# MSP_Power_Program.net
KiCad netlist of a schematic drawn in Altium Designer
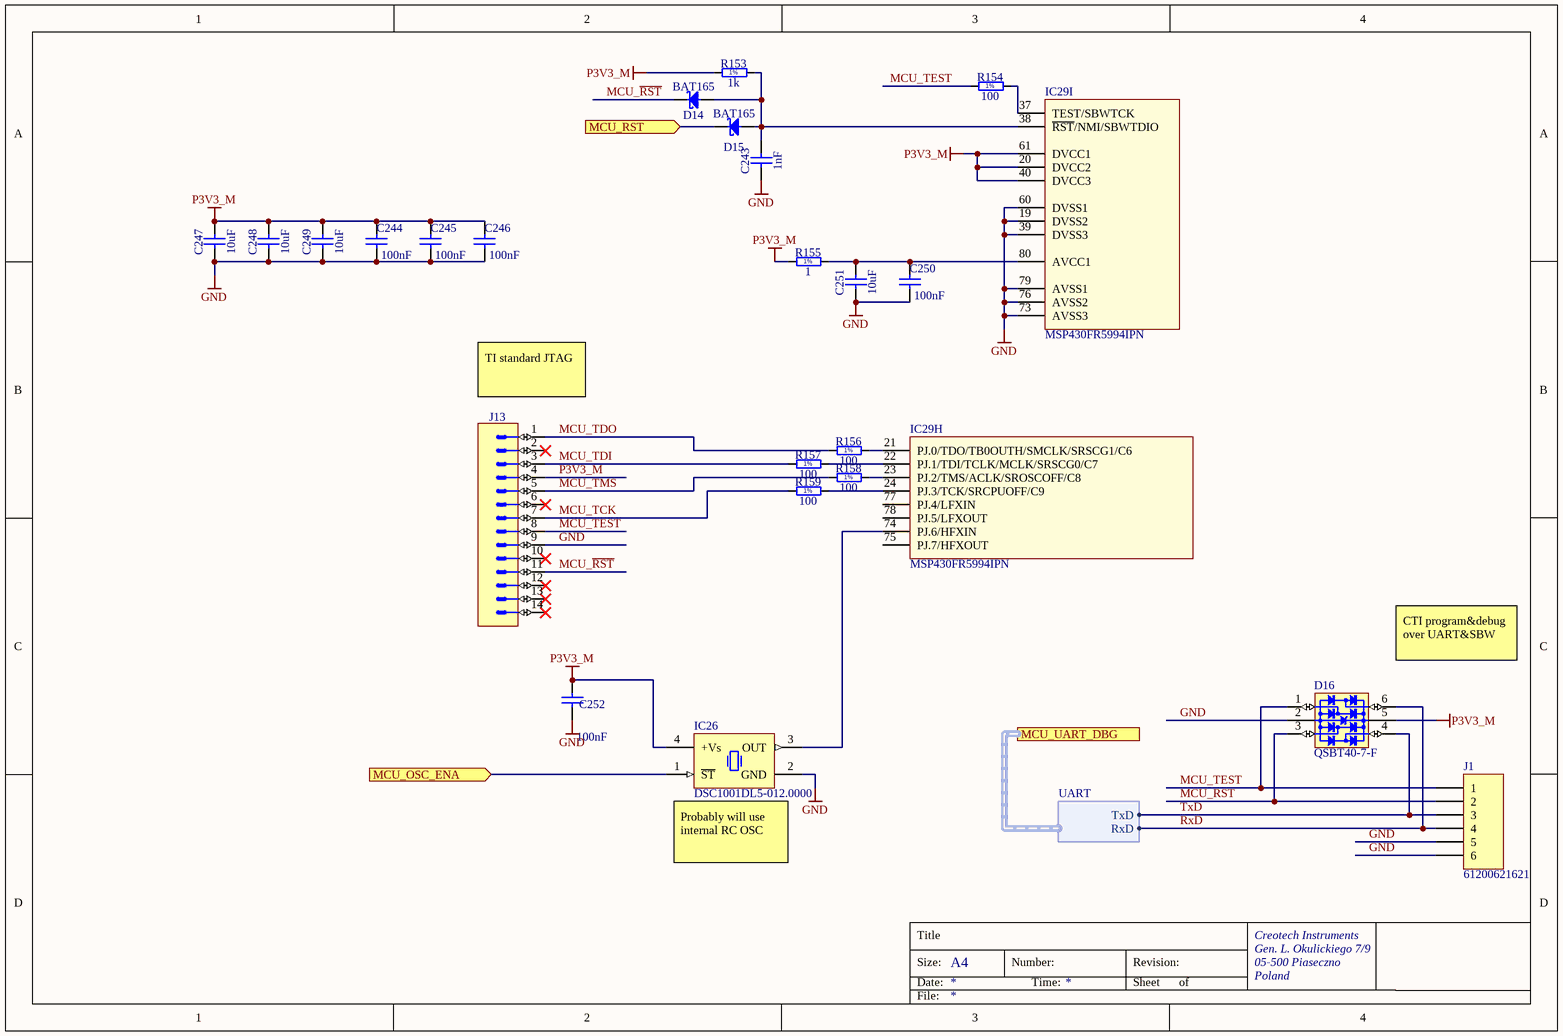
[diagram p0: MSP_Power_Program.SchDoc]

(export (version "E")
  (design (tool "Eeschema 10.0.6"))
  (components
    (comp (ref "C243")
      (value "1nF")
      (footprint "CAPC1608X87N")
      (description "Non-polarised capacitor")
      (fields
        (field (name "PART NUMBER") "CC0603_1NF_50V_10%_X7R")
        (field (name "VOLTAGE") "50V")
        (field (name "AUTHOR") "CERN DEM JLC")
      )
      (libsource (lib "Capacitors") (part "Capacitor - non polarized"))
    )
    (comp (ref "C244")
      (value "100nF")
      (footprint "CAPC1608X87N")
      (description "Non-polarised capacitor")
      (fields
        (field (name "PART NUMBER") "CC0603_100NF_50V_10%_X7R")
        (field (name "VOLTAGE") "50V")
        (field (name "AUTHOR") "CERN DEM JLC")
      )
      (libsource (lib "Capacitors") (part "Capacitor - non polarized"))
    )
    (comp (ref "C245")
      (value "100nF")
      (footprint "CAPC1608X87N")
      (description "Non-polarised capacitor")
      (fields
        (field (name "PART NUMBER") "CC0603_100NF_50V_10%_X7R")
        (field (name "VOLTAGE") "50V")
        (field (name "AUTHOR") "CERN DEM JLC")
      )
      (libsource (lib "Capacitors") (part "Capacitor - non polarized"))
    )
    (comp (ref "C246")
      (value "100nF")
      (footprint "CAPC1608X87N")
      (description "Non-polarised capacitor")
      (fields
        (field (name "PART NUMBER") "CC0603_100NF_50V_10%_X7R")
        (field (name "VOLTAGE") "50V")
        (field (name "AUTHOR") "CERN DEM JLC")
      )
      (libsource (lib "Capacitors") (part "Capacitor - non polarized"))
    )
    (comp (ref "C247")
      (value "10uF")
      (footprint "CAPC1608X80N")
      (description "Non-polarised capacitor")
      (fields
        (field (name "PART NUMBER") "CC0603_10UF_16V_20%_X5R")
        (field (name "VOLTAGE") "16V")
        (field (name "AUTHOR") "CERN DEM MR")
      )
      (libsource (lib "Capacitors") (part "Capacitor - non polarized"))
    )
    (comp (ref "C248")
      (value "10uF")
      (footprint "CAPC1608X80N")
      (description "Non-polarised capacitor")
      (fields
        (field (name "PART NUMBER") "CC0603_10UF_16V_20%_X5R")
        (field (name "VOLTAGE") "16V")
        (field (name "AUTHOR") "CERN DEM MR")
      )
      (libsource (lib "Capacitors") (part "Capacitor - non polarized"))
    )
    (comp (ref "C249")
      (value "10uF")
      (footprint "CAPC1608X80N")
      (description "Non-polarised capacitor")
      (fields
        (field (name "PART NUMBER") "CC0603_10UF_16V_20%_X5R")
        (field (name "VOLTAGE") "16V")
        (field (name "AUTHOR") "CERN DEM MR")
      )
      (libsource (lib "Capacitors") (part "Capacitor - non polarized"))
    )
    (comp (ref "C250")
      (value "100nF")
      (footprint "CAPC1608X87N")
      (description "Non-polarised capacitor")
      (fields
        (field (name "PART NUMBER") "CC0603_100NF_50V_10%_X7R")
        (field (name "VOLTAGE") "50V")
        (field (name "AUTHOR") "CERN DEM JLC")
      )
      (libsource (lib "Capacitors") (part "Capacitor - non polarized"))
    )
    (comp (ref "C251")
      (value "10uF")
      (footprint "CAPC1608X80N")
      (description "Non-polarised capacitor")
      (fields
        (field (name "PART NUMBER") "CC0603_10UF_16V_20%_X5R")
        (field (name "VOLTAGE") "16V")
        (field (name "AUTHOR") "CERN DEM MR")
      )
      (libsource (lib "Capacitors") (part "Capacitor - non polarized"))
    )
    (comp (ref "C252")
      (value "100nF")
      (footprint "CAPC1608X87N")
      (description "Non-polarised capacitor")
      (fields
        (field (name "PART NUMBER") "CC0603_100NF_50V_10%_X7R")
        (field (name "VOLTAGE") "50V")
        (field (name "AUTHOR") "CERN DEM JLC")
      )
      (libsource (lib "Capacitors") (part "Capacitor - non polarized"))
    )
    (comp (ref "D14")
      (value "BAT165")
      (footprint "SOD2512X110N")
      (description "Schottky Diode")
      (fields
        (field (name "VOLTAGE") "40V")
        (field (name "POWER") "750mA")
        (field (name "AUTHOR") "CERN DEM JLC")
      )
      (libsource (lib "ICs And Semiconductors") (part "Diode Schottky"))
    )
    (comp (ref "D15")
      (value "BAT165")
      (footprint "SOD2512X110N")
      (description "Schottky Diode")
      (fields
        (field (name "VOLTAGE") "40V")
        (field (name "POWER") "750mA")
        (field (name "AUTHOR") "CERN DEM JLC")
      )
      (libsource (lib "ICs And Semiconductors") (part "Diode Schottky"))
    )
    (comp (ref "D16")
      (value "QSBT40-7-F")
      (footprint "SOT65P210X110-6N")
      (libsource (lib "LIBRARY_SCH") (part "D_TVS_QSBT40-7-F"))
    )
    (comp (ref "IC26")
      (value "DSC1001DL5-012.0000")
      (footprint "OSC_MICREL_2520")
      (description "MEMS Oscillator 12MHz")
      (fields (field (name "MANUFACTURER") "Micrel"))
      (libsource (lib "LIBRARY_SCH") (part "OSC_DSC1001DL5-012.0000"))
    )
    (comp (ref "IC29")
      (value "MSP430FR5994IPN")
      (footprint "PQFP50P1400X1400-80N")
      (fields (field (name "MANUFACTURER") "TI"))
      (libsource (lib "LIBRARY_SCH") (part "UPC_MSP430FR5994IPN"))
    )
    (comp (ref "J1")
      (value "61200621621")
      (footprint "61200621621")
      (description "6 pin male socket 2.54 IDC")
      (libsource (lib "LIBRARY_SCH") (part "CON_IDC_6_61200621621"))
    )
    (comp (ref "J13")
      (value "Header 14")
      (footprint "3M_N2514-6002RB")
      (description "Connector 14 Male")
      (fields
        (field (name "PART NUMBER") "3M_N2514-6002RB")
        (field (name "MANUFACTURER") "3M")
        (field (name "AUTHOR") "CERN DEM JLC")
      )
      (libsource (lib "Connectors") (part "Connector 14 Male"))
    )
    (comp (ref "R153")
      (value "1k")
      (footprint "RESC1608X55N")
      (description "Resistor - 1%")
      (fields
        (field (name "PART NUMBER") "R0603_1K_1%_0.1W_100PPM")
        (field (name "POWER") "0.1W")
        (field (name "AUTHOR") "CERN DEM JLC")
      )
      (libsource (lib "Resistors") (part "Resistor - 1%"))
    )
    (comp (ref "R154")
      (value "100")
      (footprint "RESC1608X55N")
      (description "Resistor - 1%")
      (fields
        (field (name "PART NUMBER") "R0603_100R_1%_0.1W_100PPM")
        (field (name "POWER") "0.1W")
        (field (name "AUTHOR") "CERN DEM JLC")
      )
      (libsource (lib "Resistors") (part "Resistor - 1%"))
    )
    (comp (ref "R155")
      (value "1")
      (footprint "RESC1608X55N")
      (description "Resistor - 1%")
      (fields
        (field (name "PART NUMBER") "R0603_1R_1%_0.1W_200PPM")
        (field (name "POWER") "0.1W")
        (field (name "AUTHOR") "CERN DEM JLC")
      )
      (libsource (lib "Resistors") (part "Resistor - 1%"))
    )
    (comp (ref "R156")
      (value "100")
      (footprint "RESC1608X55N")
      (description "Resistor - 1%")
      (fields
        (field (name "PART NUMBER") "R0603_100R_1%_0.1W_100PPM")
        (field (name "POWER") "0.1W")
        (field (name "AUTHOR") "CERN DEM JLC")
      )
      (libsource (lib "Resistors") (part "Resistor - 1%"))
    )
    (comp (ref "R157")
      (value "100")
      (footprint "RESC1608X55N")
      (description "Resistor - 1%")
      (fields
        (field (name "PART NUMBER") "R0603_100R_1%_0.1W_100PPM")
        (field (name "POWER") "0.1W")
        (field (name "AUTHOR") "CERN DEM JLC")
      )
      (libsource (lib "Resistors") (part "Resistor - 1%"))
    )
    (comp (ref "R158")
      (value "100")
      (footprint "RESC1608X55N")
      (description "Resistor - 1%")
      (fields
        (field (name "PART NUMBER") "R0603_100R_1%_0.1W_100PPM")
        (field (name "POWER") "0.1W")
        (field (name "AUTHOR") "CERN DEM JLC")
      )
      (libsource (lib "Resistors") (part "Resistor - 1%"))
    )
    (comp (ref "R159")
      (value "100")
      (footprint "RESC1608X55N")
      (description "Resistor - 1%")
      (fields
        (field (name "PART NUMBER") "R0603_100R_1%_0.1W_100PPM")
        (field (name "POWER") "0.1W")
        (field (name "AUTHOR") "CERN DEM JLC")
      )
      (libsource (lib "Resistors") (part "Resistor - 1%"))
    )
  )
  (nets
    (net (code "2") (name "/MCU_OSC_ENA") (class "Default")
      (node (ref "IC26") (pin "1") (pinfunction "ST_1") (pintype "input"))
    )
    (net (code "3") (name "/MCU_RST") (class "Default")
      (node (ref "D15") (pin "1") (pinfunction "C_1") (pintype "passive"))
    )
    (net (code "4") (name "/MCU_TCK") (class "Default")
      (node (ref "J13") (pin "7") (pinfunction "7_7") (pintype "bidirectional"))
      (node (ref "R159") (pin "1") (pinfunction "1_1") (pintype "passive"))
    )
    (net (code "5") (name "/MCU_TDI") (class "Default")
      (node (ref "J13") (pin "3") (pinfunction "3_3") (pintype "bidirectional"))
      (node (ref "R157") (pin "1") (pinfunction "1_1") (pintype "passive"))
    )
    (net (code "6") (name "/MCU_TDO") (class "Default")
      (node (ref "J13") (pin "1") (pinfunction "1_1") (pintype "bidirectional"))
      (node (ref "R156") (pin "1") (pinfunction "1_1") (pintype "passive"))
    )
    (net (code "7") (name "/MCU_TEST") (class "Default")
      (node (ref "D16") (pin "1") (pinfunction "I/O1_1") (pintype "bidirectional"))
      (node (ref "J1") (pin "1") (pinfunction "1_1") (pintype "passive"))
      (node (ref "J13") (pin "8") (pinfunction "8_8") (pintype "bidirectional"))
      (node (ref "R154") (pin "1") (pinfunction "1_1") (pintype "passive"))
    )
    (net (code "8") (name "/MCU_TMS") (class "Default")
      (node (ref "J13") (pin "5") (pinfunction "5_5") (pintype "bidirectional"))
      (node (ref "R158") (pin "1") (pinfunction "1_1") (pintype "passive"))
    )
    (net (code "9") (name "/MCU_~{RST}") (class "Default")
      (node (ref "D14") (pin "1") (pinfunction "C_1") (pintype "passive"))
      (node (ref "D16") (pin "3") (pinfunction "I/O2_3") (pintype "bidirectional"))
      (node (ref "J1") (pin "2") (pinfunction "2_2") (pintype "passive"))
      (node (ref "J13") (pin "11") (pinfunction "11_11") (pintype "bidirectional"))
    )
    (net (code "10") (name "/RxD") (class "Default")
      (node (ref "D16") (pin "6") (pinfunction "I/O4_6") (pintype "bidirectional"))
      (node (ref "J1") (pin "4") (pinfunction "4_4") (pintype "passive"))
    )
    (net (code "11") (name "/TxD") (class "Default")
      (node (ref "D16") (pin "4") (pinfunction "I/O3_4") (pintype "bidirectional"))
      (node (ref "J1") (pin "3") (pinfunction "3_3") (pintype "passive"))
    )
    (net (code "13") (name "GND") (class "Default")
      (node (ref "C243") (pin "1") (pinfunction "1_1") (pintype "passive"))
      (node (ref "C244") (pin "1") (pinfunction "1_1") (pintype "passive"))
      (node (ref "C245") (pin "1") (pinfunction "1_1") (pintype "passive"))
      (node (ref "C246") (pin "1") (pinfunction "1_1") (pintype "passive"))
      (node (ref "C247") (pin "1") (pinfunction "1_1") (pintype "passive"))
      (node (ref "C248") (pin "1") (pinfunction "1_1") (pintype "passive"))
      (node (ref "C249") (pin "1") (pinfunction "1_1") (pintype "passive"))
      (node (ref "C250") (pin "1") (pinfunction "1_1") (pintype "passive"))
      (node (ref "C251") (pin "1") (pinfunction "1_1") (pintype "passive"))
      (node (ref "C252") (pin "1") (pinfunction "1_1") (pintype "passive"))
      (node (ref "D16") (pin "2") (pinfunction "GND_2") (pintype "power_in"))
      (node (ref "IC26") (pin "2") (pinfunction "GND_2") (pintype "power_in"))
      (node (ref "IC29") (pin "19") (pinfunction "DVSS2_19") (pintype "passive"))
      (node (ref "IC29") (pin "39") (pinfunction "DVSS3_39") (pintype "passive"))
      (node (ref "IC29") (pin "60") (pinfunction "DVSS1_60") (pintype "passive"))
      (node (ref "IC29") (pin "73") (pinfunction "AVSS3_73") (pintype "passive"))
      (node (ref "IC29") (pin "76") (pinfunction "AVSS2_76") (pintype "passive"))
      (node (ref "IC29") (pin "79") (pinfunction "AVSS1_79") (pintype "passive"))
      (node (ref "J1") (pin "5") (pinfunction "5_5") (pintype "passive"))
      (node (ref "J1") (pin "6") (pinfunction "6_6") (pintype "passive"))
      (node (ref "J13") (pin "9") (pinfunction "9_9") (pintype "bidirectional"))
    )
    (net (code "14") (name "Net-(D14-A)") (class "Default")
      (node (ref "C243") (pin "2") (pinfunction "2_2") (pintype "passive"))
      (node (ref "D14") (pin "2") (pinfunction "A_2") (pintype "passive"))
      (node (ref "D15") (pin "2") (pinfunction "A_2") (pintype "passive"))
      (node (ref "IC29") (pin "38") (pinfunction "~{RST}/NMI/SBWTDIO_38") (pintype "passive"))
      (node (ref "R153") (pin "2") (pinfunction "2_2") (pintype "passive"))
    )
    (net (code "15") (name "Net-(IC26-OUT)") (class "Default")
      (node (ref "IC26") (pin "3") (pinfunction "OUT_3") (pintype "output"))
      (node (ref "IC29") (pin "74") (pinfunction "PJ.6/HFXIN_74") (pintype "passive"))
    )
    (net (code "16") (name "Net-(IC29H-PJ.0{slash}TDO{slash}TB0OUTH{slash}SMCLK{slash}SRSCG1{slash}C6)") (class "Default")
      (node (ref "IC29") (pin "21") (pinfunction "PJ.0/TDO/TB0OUTH/SMCLK/SRSCG1/C6_21") (pintype "passive"))
      (node (ref "R156") (pin "2") (pinfunction "2_2") (pintype "passive"))
    )
    (net (code "17") (name "Net-(IC29H-PJ.1{slash}TDI{slash}TCLK{slash}MCLK{slash}SRSCG0{slash}C7)") (class "Default")
      (node (ref "IC29") (pin "22") (pinfunction "PJ.1/TDI/TCLK/MCLK/SRSCG0/C7_22") (pintype "passive"))
      (node (ref "R157") (pin "2") (pinfunction "2_2") (pintype "passive"))
    )
    (net (code "18") (name "Net-(IC29H-PJ.2{slash}TMS{slash}ACLK{slash}SROSCOFF{slash}C8)") (class "Default")
      (node (ref "IC29") (pin "23") (pinfunction "PJ.2/TMS/ACLK/SROSCOFF/C8_23") (pintype "passive"))
      (node (ref "R158") (pin "2") (pinfunction "2_2") (pintype "passive"))
    )
    (net (code "19") (name "Net-(IC29H-PJ.3{slash}TCK{slash}SRCPUOFF{slash}C9)") (class "Default")
      (node (ref "IC29") (pin "24") (pinfunction "PJ.3/TCK/SRCPUOFF/C9_24") (pintype "passive"))
      (node (ref "R159") (pin "2") (pinfunction "2_2") (pintype "passive"))
    )
    (net (code "20") (name "Net-(IC29I-AVCC1)") (class "Default")
      (node (ref "C250") (pin "2") (pinfunction "2_2") (pintype "passive"))
      (node (ref "C251") (pin "2") (pinfunction "2_2") (pintype "passive"))
      (node (ref "IC29") (pin "80") (pinfunction "AVCC1_80") (pintype "passive"))
      (node (ref "R155") (pin "2") (pinfunction "2_2") (pintype "passive"))
    )
    (net (code "21") (name "Net-(IC29I-TEST{slash}SBWTCK)") (class "Default")
      (node (ref "IC29") (pin "37") (pinfunction "TEST/SBWTCK_37") (pintype "passive"))
      (node (ref "R154") (pin "2") (pinfunction "2_2") (pintype "passive"))
    )
    (net (code "22") (name "P3V3_M") (class "Default")
      (node (ref "C244") (pin "2") (pinfunction "2_2") (pintype "passive"))
      (node (ref "C245") (pin "2") (pinfunction "2_2") (pintype "passive"))
      (node (ref "C246") (pin "2") (pinfunction "2_2") (pintype "passive"))
      (node (ref "C247") (pin "2") (pinfunction "2_2") (pintype "passive"))
      (node (ref "C248") (pin "2") (pinfunction "2_2") (pintype "passive"))
      (node (ref "C249") (pin "2") (pinfunction "2_2") (pintype "passive"))
      (node (ref "C252") (pin "2") (pinfunction "2_2") (pintype "passive"))
      (node (ref "D16") (pin "5") (pinfunction "VBUS_5") (pintype "power_in"))
      (node (ref "IC26") (pin "4") (pinfunction "+Vs_4") (pintype "power_in"))
      (node (ref "IC29") (pin "20") (pinfunction "DVCC2_20") (pintype "passive"))
      (node (ref "IC29") (pin "40") (pinfunction "DVCC3_40") (pintype "passive"))
      (node (ref "IC29") (pin "61") (pinfunction "DVCC1_61") (pintype "passive"))
      (node (ref "J13") (pin "4") (pinfunction "4_4") (pintype "bidirectional"))
      (node (ref "R153") (pin "1") (pinfunction "1_1") (pintype "passive"))
      (node (ref "R155") (pin "1") (pinfunction "1_1") (pintype "passive"))
    )
    (net (code "23") (name "unconnected-(IC29H-PJ.4{slash}LFXIN-Pad77)") (class "Default")
      (node (ref "IC29") (pin "77") (pinfunction "PJ.4/LFXIN_77") (pintype "passive"))
    )
    (net (code "24") (name "unconnected-(IC29H-PJ.5{slash}LFXOUT-Pad78)") (class "Default")
      (node (ref "IC29") (pin "78") (pinfunction "PJ.5/LFXOUT_78") (pintype "passive"))
    )
    (net (code "25") (name "unconnected-(IC29H-PJ.7{slash}HFXOUT-Pad75)") (class "Default")
      (node (ref "IC29") (pin "75") (pinfunction "PJ.7/HFXOUT_75") (pintype "passive"))
    )
    (net (code "26") (name "unconnected-(J13-Pad2)") (class "Default")
      (node (ref "J13") (pin "2") (pinfunction "2_2") (pintype "bidirectional+no_connect"))
    )
    (net (code "27") (name "unconnected-(J13-Pad6)") (class "Default")
      (node (ref "J13") (pin "6") (pinfunction "6_6") (pintype "bidirectional+no_connect"))
    )
    (net (code "28") (name "unconnected-(J13-Pad10)") (class "Default")
      (node (ref "J13") (pin "10") (pinfunction "10_10") (pintype "bidirectional+no_connect"))
    )
    (net (code "29") (name "unconnected-(J13-Pad12)") (class "Default")
      (node (ref "J13") (pin "12") (pinfunction "12_12") (pintype "bidirectional+no_connect"))
    )
    (net (code "30") (name "unconnected-(J13-Pad13)") (class "Default")
      (node (ref "J13") (pin "13") (pinfunction "13_13") (pintype "bidirectional+no_connect"))
    )
    (net (code "31") (name "unconnected-(J13-Pad14)") (class "Default")
      (node (ref "J13") (pin "14") (pinfunction "14_14") (pintype "bidirectional+no_connect"))
    )
  )
)
